# PT_Buffer.net
KiCad netlist of a schematic drawn in Altium Designer
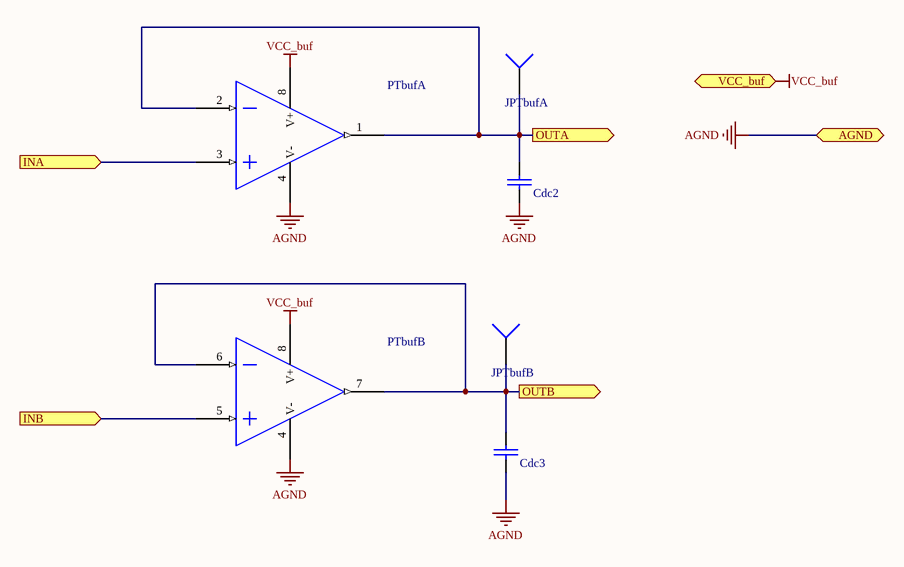
[diagram p0: PT_Buffer.SchDoc]

(export (version "E")
  (design (tool "Eeschema 10.0.6"))
  (components
    (comp (ref "Cdc2")
      (value "47nF")
      (footprint "ECE-CAPC2012-0805SM")
      (description "CAP CER 47nF 50V X7R SM0805")
      (libsource (lib "Capacitos$") (part "CAP000522"))
    )
    (comp (ref "Cdc3")
      (value "47nF")
      (footprint "ECE-CAPC2012-0805SM")
      (description "CAP CER 47nF 50V X7R SM0805")
      (libsource (lib "Capacitos$") (part "CAP000522"))
    )
    (comp (ref "JPTbufA")
      (value "TEST PIN")
      (footprint "ECE-HDR1TH")
      (libsource (lib "Connectors$") (part "CON000017"))
    )
    (comp (ref "JPTbufB")
      (value "TEST PIN")
      (footprint "ECE-HDR1TH")
      (libsource (lib "Connectors$") (part "CON000017"))
    )
    (comp (ref "PTbuf")
      (value "LT6221")
      (footprint "ECE-SO8")
      (description "IC OPAMP LT6221 DUAL SM")
      (libsource (lib "OpAmps$") (part "OPA000102"))
    )
  )
  (nets
    (net (code "1") (name "/INA") (class "Default")
      (node (ref "PTbuf") (pin "3") (pinfunction "IN1(+)_3") (pintype "input"))
    )
    (net (code "2") (name "/INB") (class "Default")
      (node (ref "PTbuf") (pin "5") (pinfunction "IN2(+)_5") (pintype "input"))
    )
    (net (code "3") (name "/OUTA") (class "Default")
      (node (ref "Cdc2") (pin "1") (pinfunction "1_1") (pintype "passive"))
      (node (ref "JPTbufA") (pin "1") (pinfunction "1_1") (pintype "passive"))
      (node (ref "PTbuf") (pin "1") (pinfunction "OUT1_1") (pintype "output"))
      (node (ref "PTbuf") (pin "2") (pinfunction "IN1(-)_2") (pintype "input"))
    )
    (net (code "4") (name "/OUTB") (class "Default")
      (node (ref "Cdc3") (pin "1") (pinfunction "1_1") (pintype "passive"))
      (node (ref "JPTbufB") (pin "1") (pinfunction "1_1") (pintype "passive"))
      (node (ref "PTbuf") (pin "6") (pinfunction "IN2(-)_6") (pintype "input"))
      (node (ref "PTbuf") (pin "7") (pinfunction "OUT2_7") (pintype "output"))
    )
    (net (code "5") (name "AGND") (class "Default")
      (node (ref "Cdc2") (pin "2") (pinfunction "2_2") (pintype "passive"))
      (node (ref "Cdc3") (pin "2") (pinfunction "2_2") (pintype "passive"))
      (node (ref "PTbuf") (pin "4") (pinfunction "V-_4") (pintype "power_in"))
    )
    (net (code "6") (name "VCC_buf") (class "Default")
      (node (ref "PTbuf") (pin "8") (pinfunction "V+_8") (pintype "power_in"))
    )
  )
)
